# S1_POWER.net
KiCad netlist of a schematic drawn in Altium Designer
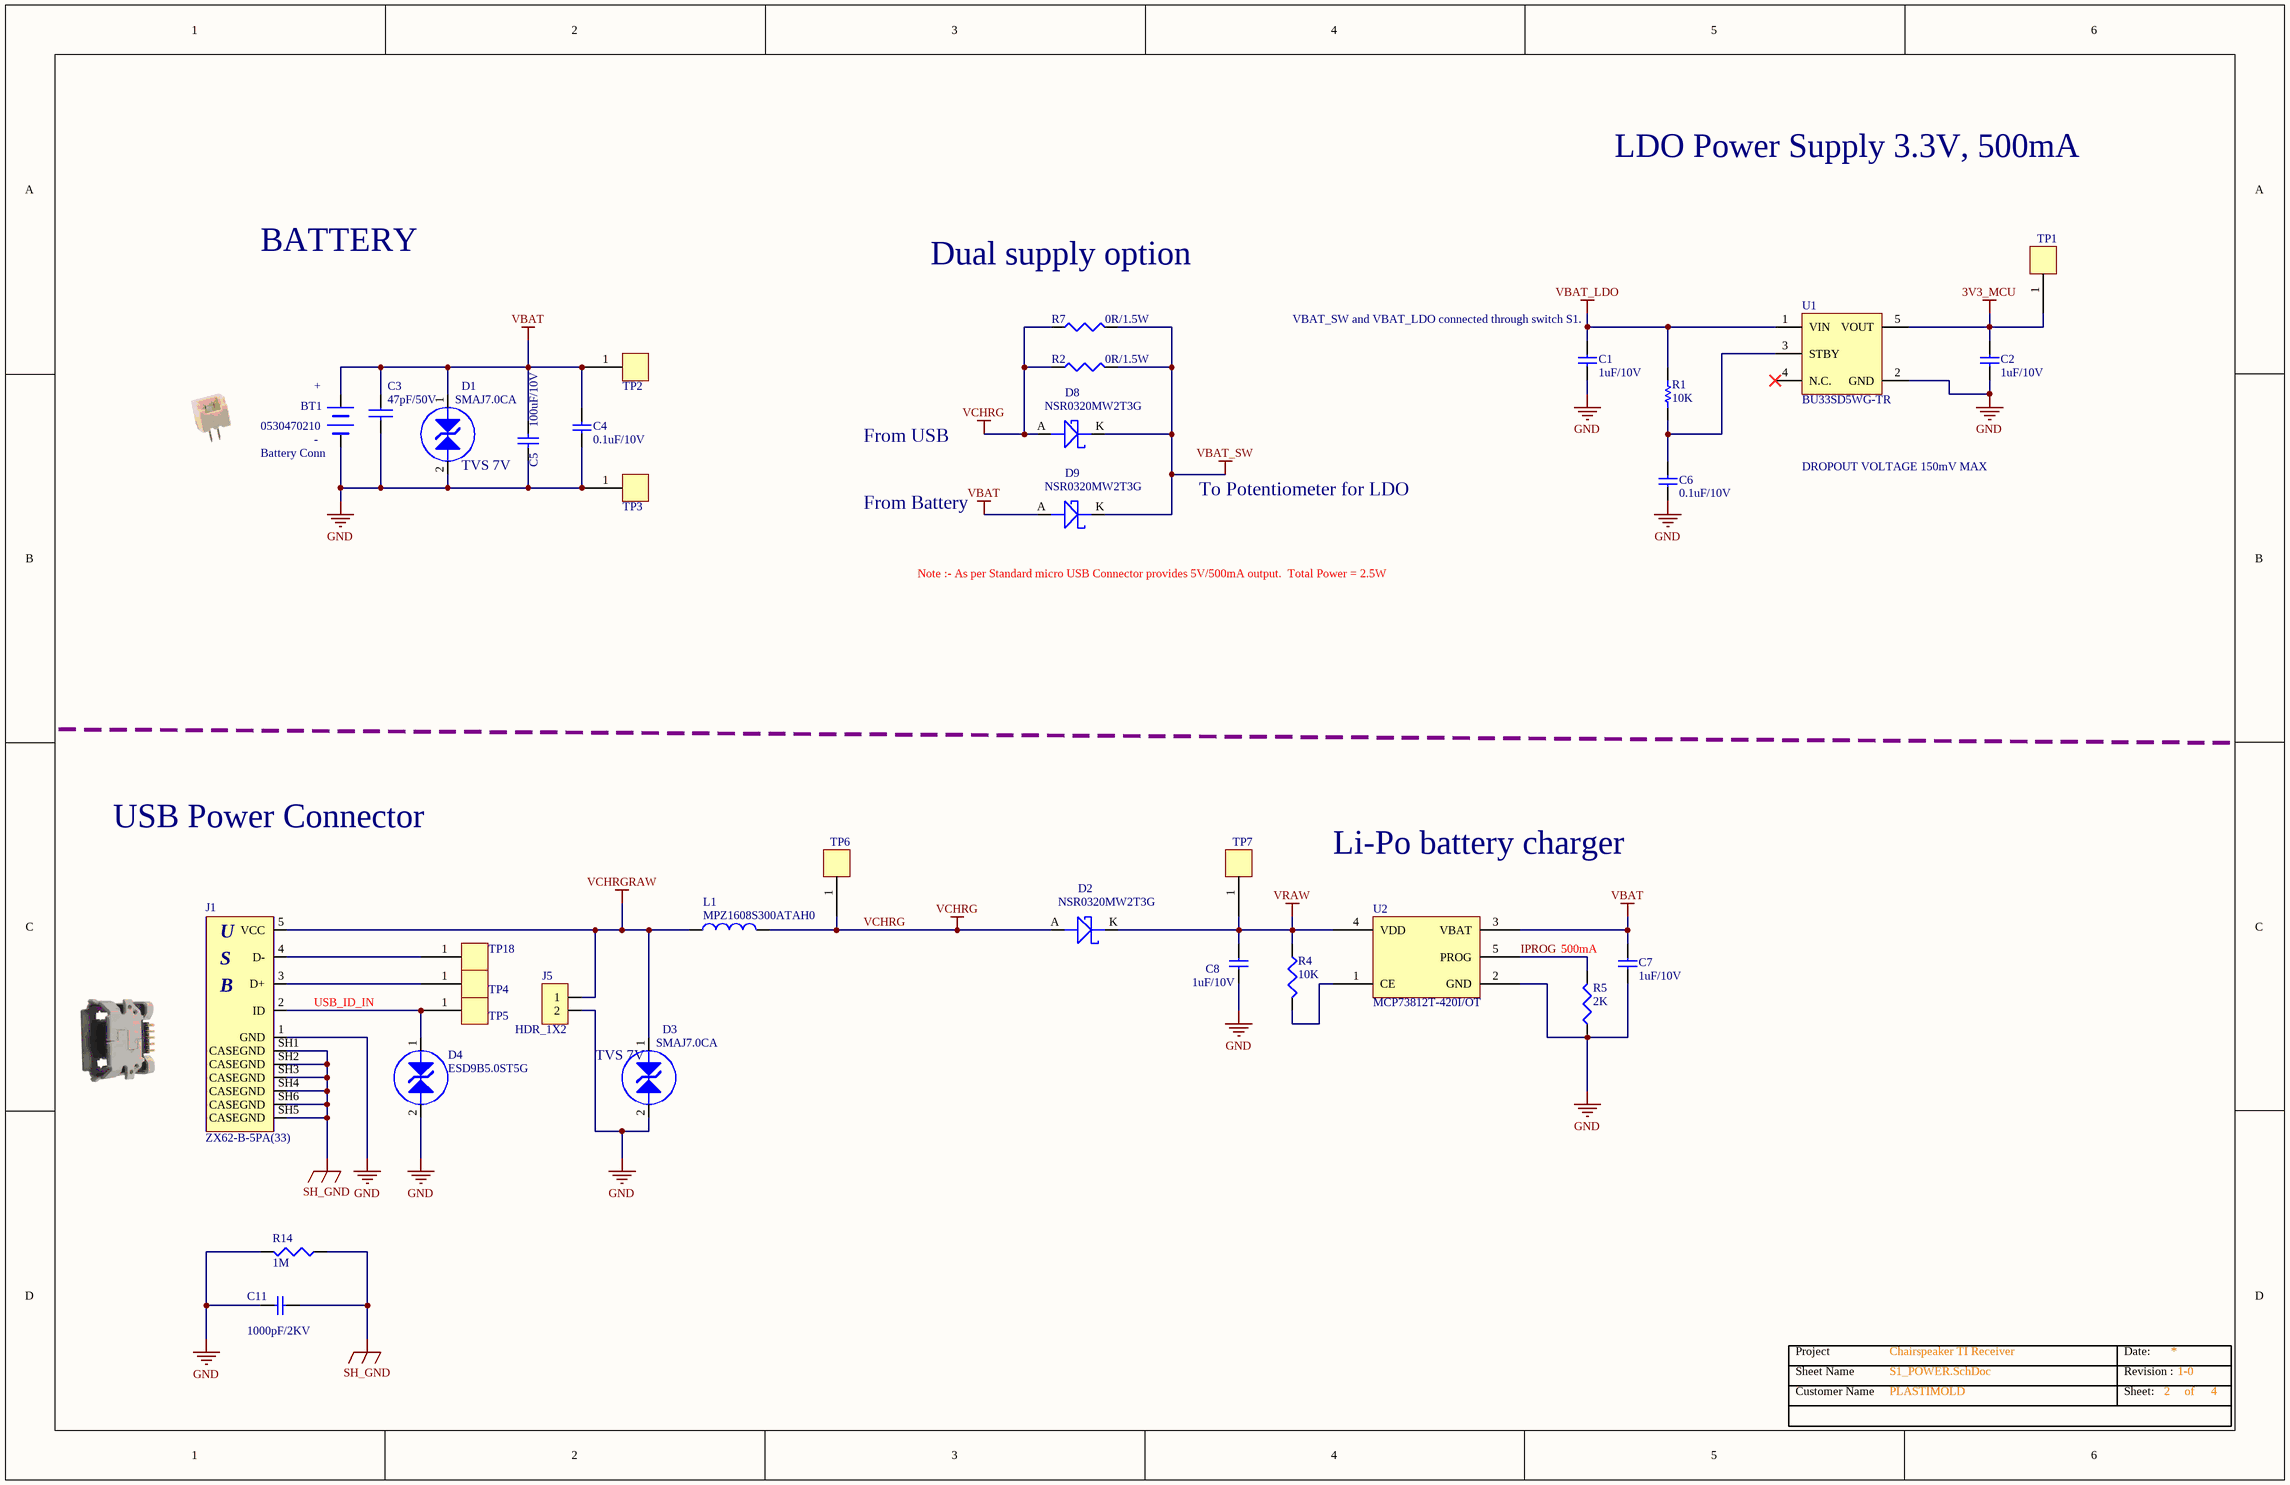
[diagram p0: S1_POWER.SchDoc]

(export (version "E")
  (design (tool "Eeschema 10.0.6"))
  (components
    (comp (ref "BT1")
      (value "0530470210")
      (footprint "0530470210")
      (description "=Description1")
      (libsource (lib "InventureTrack RC30 REV01") (part "BATTERY"))
    )
    (comp (ref "C1")
      (value "1uF/10V")
      (footprint "CAP_0402_(M1005)")
      (description "=Description1")
      (libsource (lib "Nordic Passive DB") (part "CAP"))
    )
    (comp (ref "C2")
      (value "1uF/10V")
      (footprint "CAP_0402_(M1005)")
      (description "=Description1")
      (libsource (lib "Nordic Passive DB") (part "CAP"))
    )
    (comp (ref "C3")
      (value "47pF/50V")
      (footprint "CAP_0402_(M1005)")
      (description "=Description1")
      (libsource (lib "RC50_REV0-1") (part "CAP NP"))
    )
    (comp (ref "C4")
      (value "0.1uF/10V")
      (footprint "CAP_0402_(M1005)")
      (description "=Description1")
      (libsource (lib "Nordic Passive DB") (part "CAP"))
    )
    (comp (ref "C5")
      (value "100uF/10V")
      (footprint "CAP_1210_3225")
      (description "=Description1")
      (libsource (lib "RC50_REV0-1") (part "C3216JB1A107M160AC"))
    )
    (comp (ref "C6")
      (value "0.1uF/10V")
      (footprint "CAP_0402_(M1005)")
      (description "=Description1")
      (libsource (lib "Nordic Passive DB") (part "CAP"))
    )
    (comp (ref "C7")
      (value "1uF/10V")
      (footprint "CAP_0402_(M1005)")
      (description "=Description1")
      (libsource (lib "Nordic Passive DB") (part "CAP"))
    )
    (comp (ref "C8")
      (value "1uF/10V")
      (footprint "CAP_0402_(M1005)")
      (description "=Description1")
      (libsource (lib "Nordic Passive DB") (part "CAP"))
    )
    (comp (ref "C11")
      (value "1000pF/2KV")
      (footprint "CAP_1206_(M3016)")
      (description "=Description1")
      (libsource (lib "PIEZOAMP") (part "GRM155R61A104KA01D"))
    )
    (comp (ref "D1")
      (value "SMAJ7.0CA")
      (footprint "DO-214AC (SMA)_BI_DIRECTION")
      (description "=Description1")
      (libsource (lib "APC_SCH.") (part "TVS-DIODE"))
    )
    (comp (ref "D2")
      (value "NSR0320MW2T3G")
      (footprint "SOD-323")
      (description "=Description1")
      (libsource (lib "RC50_REV0-1_INT") (part "DIODE SCHOTTKY"))
    )
    (comp (ref "D3")
      (value "SMAJ7.0CA")
      (footprint "DO-214AC (SMA)_BI_DIRECTION")
      (description "=Description1")
      (libsource (lib "APC_SCH.") (part "TVS-DIODE"))
    )
    (comp (ref "D4")
      (value "ESD9B5.0ST5G")
      (footprint "SOD-923-BI-DIRECTIONAL")
      (description "=Description1")
      (libsource (lib "APC_SCH.") (part "TVS-DIODE"))
    )
    (comp (ref "D8")
      (value "NSR0320MW2T3G")
      (footprint "SOD-323")
      (description "=Description1")
      (libsource (lib "RC50_REV0-1_INT") (part "DIODE SCHOTTKY"))
    )
    (comp (ref "D9")
      (value "NSR0320MW2T3G")
      (footprint "SOD-323")
      (description "=Description1")
      (libsource (lib "RC50_REV0-1_INT") (part "DIODE SCHOTTKY"))
    )
    (comp (ref "J1")
      (value "ZX62-B-5PA(33)")
      (footprint "USB_MICRODBG")
      (description "=Description1")
      (libsource (lib "RC40 REV0-2") (part "CONN_USB_MINI_B"))
    )
    (comp (ref "J5")
      (value "HDR_1X2")
      (footprint "HDR_1X2")
      (description "=Description1")
      (libsource (lib "Symbol") (part "HDR_1X2"))
    )
    (comp (ref "L1")
      (value "MPZ1608S300ATAH0")
      (footprint "IND_0603_(M1608)")
      (description "=Description1")
      (libsource (lib "APC_SCH") (part "FERRITE BEAD"))
    )
    (comp (ref "R1")
      (value "10K")
      (footprint "RES_0402_(M1005)")
      (description "=Description1")
      (libsource (lib "Symbol") (part "RESISTOR"))
    )
    (comp (ref "R2")
      (value "0R/1.5W")
      (footprint "RES_2512_(M6432)")
      (description "=Description1")
      (fields (field (name "Comment") "0R"))
      (libsource (lib "iTREE3") (part "RES_0R"))
    )
    (comp (ref "R4")
      (value "10K")
      (footprint "RES_0402_(M1005)")
      (description "=Description1")
      (libsource (lib "APC_SCH") (part "RES"))
    )
    (comp (ref "R5")
      (value "2K")
      (footprint "RES_0402_(M1005)")
      (description "=Description1")
      (libsource (lib "APC_SCH") (part "RES"))
    )
    (comp (ref "R7")
      (value "0R/1.5W")
      (footprint "RES_2512_(M6432)")
      (description "=Description1")
      (fields (field (name "Comment") "0R"))
      (libsource (lib "iTREE3") (part "RES_0R"))
    )
    (comp (ref "R14")
      (value "1M")
      (footprint "RES_0402_(M1005)")
      (description "=Description1")
      (libsource (lib "APC_SCH") (part "RES"))
    )
    (comp (ref "TP1")
      (value "TP")
      (footprint "TestP SM 30MIL ROUND")
      (description "=Description1")
      (libsource (lib "") (part "TP_1"))
    )
    (comp (ref "TP2")
      (value "TP")
      (footprint "TestP SM 30MIL ROUND")
      (description "=Description1")
      (libsource (lib "RC30 REv01") (part "TP"))
    )
    (comp (ref "TP3")
      (value "TP")
      (footprint "TestP SM 30MIL ROUND")
      (description "=Description1")
      (libsource (lib "RC30 REv01") (part "TP"))
    )
    (comp (ref "TP4")
      (value "TP")
      (footprint "TestP SM 30MIL ROUND")
      (description "=Description1")
      (libsource (lib "RC30 REv01") (part "TP"))
    )
    (comp (ref "TP5")
      (value "TP")
      (footprint "TestP SM 30MIL ROUND")
      (description "=Description1")
      (libsource (lib "RC30 REv01") (part "TP"))
    )
    (comp (ref "TP6")
      (value "TP")
      (footprint "TestP SM 30MIL ROUND")
      (description "=Description1")
      (libsource (lib "") (part "TP_1"))
    )
    (comp (ref "TP7")
      (value "TP")
      (footprint "TestP SM 30MIL ROUND")
      (description "=Description1")
      (libsource (lib "") (part "TP_1"))
    )
    (comp (ref "TP18")
      (value "TP")
      (footprint "TestP SM 30MIL ROUND")
      (description "=Description1")
      (libsource (lib "RC30 REv01") (part "TP"))
    )
    (comp (ref "U1")
      (value "BU33SD5WG-TR")
      (footprint "SSOP5")
      (description "=Description1")
      (libsource (lib "TV-Pillow_REV0-1") (part "BU33SD5WG-TR"))
    )
    (comp (ref "U2")
      (value "MCP73812T-420I/OT")
      (footprint "SOT23-5")
      (description "=Description1")
      (libsource (lib "InventureTrack RC30 REV01") (part "CHG_MCP73812"))
    )
  )
  (nets
    (net (code "1") (name "/IPROG") (class "Default")
      (node (ref "R5") (pin "2") (pintype "passive"))
      (node (ref "U2") (pin "5") (pinfunction "PROG_5") (pintype "passive"))
    )
    (net (code "2") (name "/USB_ID_IN") (class "Default")
      (node (ref "D4") (pin "1") (pintype "passive"))
      (node (ref "J1") (pin "2") (pinfunction "ID_2") (pintype "power_in"))
      (node (ref "TP5") (pin "1") (pintype "passive"))
    )
    (net (code "3") (name "3V3_MCU") (class "Default")
      (node (ref "C2") (pin "2") (pinfunction "2_2") (pintype "passive"))
      (node (ref "TP1") (pin "1") (pintype "passive"))
      (node (ref "U1") (pin "5") (pinfunction "VOUT_5") (pintype "passive"))
    )
    (net (code "4") (name "GND") (class "Default")
      (node (ref "BT1") (pin "1") (pintype "passive"))
      (node (ref "C1") (pin "1") (pinfunction "1_1") (pintype "passive"))
      (node (ref "C11") (pin "1") (pinfunction "1_1") (pintype "passive"))
      (node (ref "C2") (pin "1") (pinfunction "1_1") (pintype "passive"))
      (node (ref "C3") (pin "2") (pinfunction "2_2") (pintype "passive"))
      (node (ref "C4") (pin "2") (pinfunction "2_2") (pintype "passive"))
      (node (ref "C5") (pin "2") (pinfunction "2_2") (pintype "passive"))
      (node (ref "C6") (pin "2") (pinfunction "2_2") (pintype "passive"))
      (node (ref "C7") (pin "1") (pinfunction "1_1") (pintype "passive"))
      (node (ref "C8") (pin "1") (pinfunction "1_1") (pintype "passive"))
      (node (ref "D1") (pin "2") (pintype "passive"))
      (node (ref "D3") (pin "2") (pintype "passive"))
      (node (ref "D4") (pin "2") (pintype "passive"))
      (node (ref "J1") (pin "1") (pinfunction "GND_1") (pintype "power_in"))
      (node (ref "J5") (pin "2") (pinfunction "2_2") (pintype "passive"))
      (node (ref "R14") (pin "1") (pintype "passive"))
      (node (ref "R5") (pin "1") (pintype "passive"))
      (node (ref "TP3") (pin "1") (pintype "passive"))
      (node (ref "U1") (pin "2") (pinfunction "GND_2") (pintype "passive"))
      (node (ref "U2") (pin "2") (pinfunction "GND_2") (pintype "power_in"))
    )
    (net (code "5") (name "Net-(J1-D+)") (class "Default")
      (node (ref "J1") (pin "3") (pinfunction "D+_3") (pintype "passive"))
      (node (ref "TP4") (pin "1") (pintype "passive"))
    )
    (net (code "6") (name "Net-(J1-D-)") (class "Default")
      (node (ref "J1") (pin "4") (pinfunction "D-_4") (pintype "passive"))
      (node (ref "TP18") (pin "1") (pintype "passive"))
    )
    (net (code "7") (name "Net-(U1-STBY)") (class "Default")
      (node (ref "C6") (pin "1") (pinfunction "1_1") (pintype "passive"))
      (node (ref "R1") (pin "2") (pinfunction "2_2") (pintype "passive"))
      (node (ref "U1") (pin "3") (pinfunction "STBY_3") (pintype "passive"))
    )
    (net (code "8") (name "Net-(U2-CE)") (class "Default")
      (node (ref "R4") (pin "2") (pintype "passive"))
      (node (ref "U2") (pin "1") (pinfunction "CE_1") (pintype "passive"))
    )
    (net (code "9") (name "SH_GND") (class "Default")
      (node (ref "C11") (pin "2") (pinfunction "2_2") (pintype "passive"))
      (node (ref "J1") (pin "SH1") (pinfunction "CASEGND_SH1") (pintype "power_in"))
      (node (ref "J1") (pin "SH2") (pinfunction "CASEGND_SH2") (pintype "power_in"))
      (node (ref "J1") (pin "SH3") (pinfunction "CASEGND_SH3") (pintype "power_in"))
      (node (ref "J1") (pin "SH4") (pinfunction "CASEGND_SH4") (pintype "power_in"))
      (node (ref "J1") (pin "SH5") (pinfunction "CASEGND_SH5") (pintype "power_in"))
      (node (ref "J1") (pin "SH6") (pinfunction "CASEGND_SH6") (pintype "power_in"))
      (node (ref "R14") (pin "2") (pintype "passive"))
    )
    (net (code "10") (name "VBAT") (class "Default")
      (node (ref "BT1") (pin "2") (pintype "passive"))
      (node (ref "C3") (pin "1") (pinfunction "1_1") (pintype "passive"))
      (node (ref "C4") (pin "1") (pinfunction "1_1") (pintype "passive"))
      (node (ref "C5") (pin "1") (pinfunction "1_1") (pintype "passive"))
      (node (ref "C7") (pin "2") (pinfunction "2_2") (pintype "passive"))
      (node (ref "D1") (pin "1") (pintype "passive"))
      (node (ref "D9") (pin "A") (pinfunction "ANOD_A") (pintype "passive"))
      (node (ref "TP2") (pin "1") (pintype "passive"))
      (node (ref "U2") (pin "3") (pinfunction "VBAT_3") (pintype "power_in"))
    )
    (net (code "11") (name "VBAT_LDO") (class "Default")
      (node (ref "C1") (pin "2") (pinfunction "2_2") (pintype "passive"))
      (node (ref "R1") (pin "1") (pinfunction "1_1") (pintype "passive"))
      (node (ref "U1") (pin "1") (pinfunction "VIN_1") (pintype "passive"))
    )
    (net (code "12") (name "VBAT_SW") (class "Default")
      (node (ref "D8") (pin "K") (pinfunction "CATH_K") (pintype "passive"))
      (node (ref "D9") (pin "K") (pinfunction "CATH_K") (pintype "passive"))
      (node (ref "R2") (pin "2") (pintype "passive"))
      (node (ref "R7") (pin "2") (pintype "passive"))
    )
    (net (code "13") (name "VCHRG") (class "Default")
      (node (ref "D2") (pin "A") (pinfunction "ANOD_A") (pintype "passive"))
      (node (ref "D8") (pin "A") (pinfunction "ANOD_A") (pintype "passive"))
      (node (ref "L1") (pin "2") (pinfunction "2_2") (pintype "passive"))
      (node (ref "R2") (pin "1") (pintype "passive"))
      (node (ref "R7") (pin "1") (pintype "passive"))
      (node (ref "TP6") (pin "1") (pintype "passive"))
    )
    (net (code "14") (name "VCHRGRAW") (class "Default")
      (node (ref "D3") (pin "1") (pintype "passive"))
      (node (ref "J1") (pin "5") (pinfunction "VCC_5") (pintype "power_in"))
      (node (ref "J5") (pin "1") (pinfunction "1_1") (pintype "passive"))
      (node (ref "L1") (pin "1") (pinfunction "1_1") (pintype "passive"))
    )
    (net (code "15") (name "VRAW") (class "Default")
      (node (ref "C8") (pin "2") (pinfunction "2_2") (pintype "passive"))
      (node (ref "D2") (pin "K") (pinfunction "CATH_K") (pintype "passive"))
      (node (ref "R4") (pin "1") (pintype "passive"))
      (node (ref "TP7") (pin "1") (pintype "passive"))
      (node (ref "U2") (pin "4") (pinfunction "VDD_4") (pintype "power_in"))
    )
    (net (code "16") (name "unconnected-(U1-N.C.-Pad4)") (class "Default")
      (node (ref "U1") (pin "4") (pinfunction "N.C._4") (pintype "passive+no_connect"))
    )
  )
)
